# EFM8_Tag-Connect.net
KiCad netlist of a schematic drawn in EAGLE
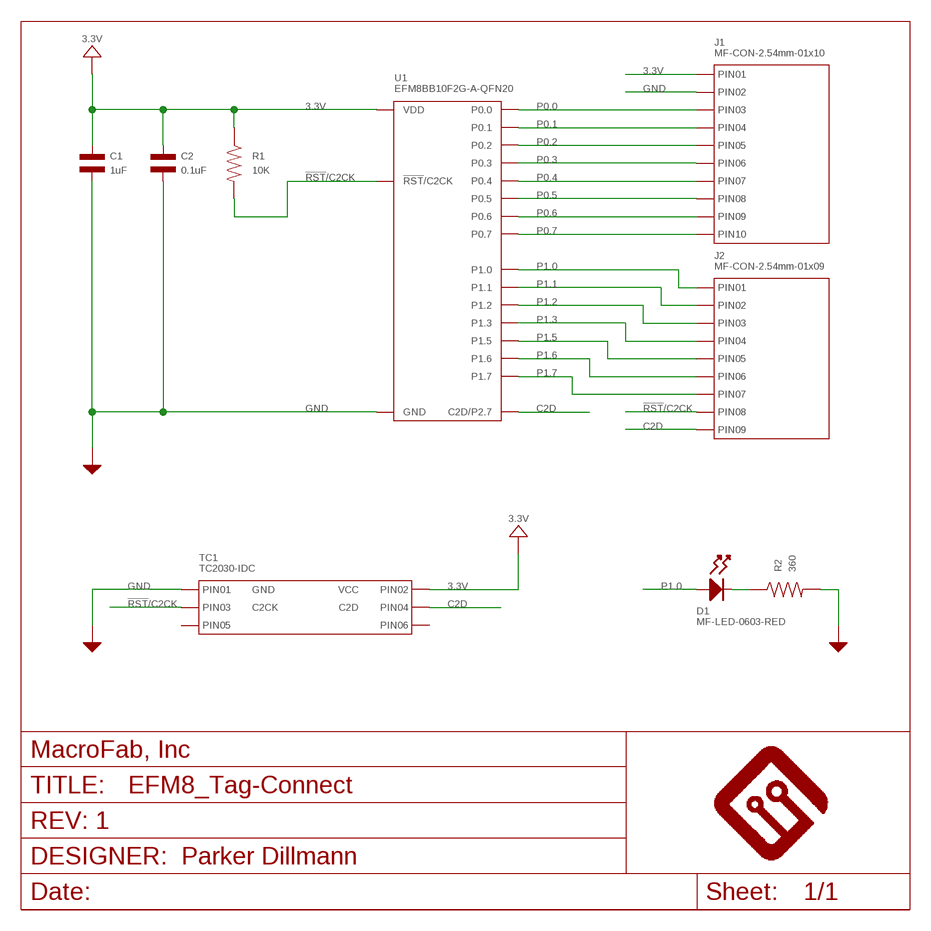
[diagram p0: schematic, sheet 1]

(export (version "E")
  (design (tool "Eeschema 10.0.6"))
  (components
    (comp (ref "C1")
      (value "1uF")
      (footprint "eagle-import:C0402")
      (fields (field (name "MPN") "MF-CAP-0402-1uF"))
      (libsource (lib "eagle-import") (part "CAPACITOR_NP_0402"))
    )
    (comp (ref "C2")
      (value "0.1uF")
      (footprint "eagle-import:C0402")
      (fields (field (name "MPN") "MF-CAP-0402-0.1uF"))
      (libsource (lib "eagle-import") (part "CAPACITOR_NP_0402"))
    )
    (comp (ref "D1")
      (value "MF-LED-0603-RED")
      (footprint "eagle-import:LED0603")
      (fields (field (name "HOUSEPART") "YES"))
      (libsource (lib "eagle-import") (part "LED_SINGLE-0603-RED"))
    )
    (comp (ref "FRAME1")
      (value "MF_FRAMEDEFAULT")
      (footprint "eagle-import:MF_FRAME_DEFAULT")
      (fields
        (field (name "HOUSEPART") "0")
        (field (name "DNAME") "Parker Dillmann")
        (field (name "REVNUM") "REV: 1")
      )
      (libsource (lib "eagle-import") (part "MF_FRAMEDEFAULT"))
    )
    (comp (ref "J1")
      (value "MF-CON-2.54mm-01x10")
      (footprint "eagle-import:PTH_2.54MM_01X10")
      (fields (field (name "HOUSEPART") "YES"))
      (libsource (lib "eagle-import") (part "CON_01X10_PTH_2.54MM"))
    )
    (comp (ref "J2")
      (value "MF-CON-2.54mm-01x09")
      (footprint "eagle-import:PTH_2.54MM_01X09")
      (fields (field (name "HOUSEPART") "YES"))
      (libsource (lib "eagle-import") (part "CON_01X09_PTH_2.54MM"))
    )
    (comp (ref "R1")
      (value "10K")
      (footprint "eagle-import:R0402")
      (fields (field (name "MPN") "MF-RES-0402-10K"))
      (libsource (lib "eagle-import") (part "RESISTOR_0402"))
    )
    (comp (ref "R2")
      (value "360")
      (footprint "eagle-import:R0402")
      (fields (field (name "MPN") "MF-RES-0402-360"))
      (libsource (lib "eagle-import") (part "RESISTOR_0402"))
    )
    (comp (ref "TC1")
      (value "TC2030-IDC")
      (footprint "eagle-import:TC2030-IDC-FP")
      (fields (field (name "HOUSEPART") "NO"))
      (libsource (lib "eagle-import") (part "CON_02X03_TC2030-IDC_SILABS2TC"))
    )
    (comp (ref "U1")
      (value "EFM8BB10F2G-A-QFN20")
      (footprint "eagle-import:EFM8BB10F(2_4_8)G-A-QFN20")
      (fields (field (name "HOUSEPART") "NO") (field (name "MPN") "EFM8BB10F2G-A-QFN20"))
      (libsource (lib "eagle-import") (part "EFM8BB10F(2/4/8)G-A-QFN20"))
    )
  )
  (nets
    (net (code "1") (name "/C2D") (class "Default")
      (node (ref "J2") (pin "P$9") (pinfunction "PIN9_P$9") (pintype "bidirectional"))
      (node (ref "TC1") (pin "P$4") (pinfunction "PIN4_P$4") (pintype "bidirectional"))
      (node (ref "U1") (pin "P$6") (pinfunction "C2D/P2.7_P$6") (pintype "bidirectional"))
    )
    (net (code "2") (name "/P0.0") (class "Default")
      (node (ref "J1") (pin "P$3") (pinfunction "PIN3_P$3") (pintype "bidirectional"))
      (node (ref "U1") (pin "P$2") (pinfunction "P0.0_P$2") (pintype "bidirectional"))
    )
    (net (code "3") (name "/P0.1") (class "Default")
      (node (ref "J1") (pin "P$4") (pinfunction "PIN4_P$4") (pintype "bidirectional"))
      (node (ref "U1") (pin "P$1") (pinfunction "P0.1_P$1") (pintype "bidirectional"))
    )
    (net (code "4") (name "/P0.2") (class "Default")
      (node (ref "J1") (pin "P$5") (pinfunction "PIN5_P$5") (pintype "bidirectional"))
      (node (ref "U1") (pin "P$20") (pinfunction "P0.2_P$20") (pintype "bidirectional"))
    )
    (net (code "5") (name "/P0.3") (class "Default")
      (node (ref "J1") (pin "P$6") (pinfunction "PIN6_P$6") (pintype "bidirectional"))
      (node (ref "U1") (pin "P$19") (pinfunction "P0.3_P$19") (pintype "bidirectional"))
    )
    (net (code "6") (name "/P0.4") (class "Default")
      (node (ref "J1") (pin "P$7") (pinfunction "PIN7_P$7") (pintype "bidirectional"))
      (node (ref "U1") (pin "P$18") (pinfunction "P0.4_P$18") (pintype "bidirectional"))
    )
    (net (code "7") (name "/P0.5") (class "Default")
      (node (ref "J1") (pin "P$8") (pinfunction "PIN8_P$8") (pintype "bidirectional"))
      (node (ref "U1") (pin "P$17") (pinfunction "P0.5_P$17") (pintype "bidirectional"))
    )
    (net (code "8") (name "/P0.6") (class "Default")
      (node (ref "J1") (pin "P$9") (pinfunction "PIN9_P$9") (pintype "bidirectional"))
      (node (ref "U1") (pin "P$16") (pinfunction "P0.6_P$16") (pintype "bidirectional"))
    )
    (net (code "9") (name "/P0.7") (class "Default")
      (node (ref "J1") (pin "P$10") (pinfunction "PIN10_P$10") (pintype "bidirectional"))
      (node (ref "U1") (pin "P$15") (pinfunction "P0.7_P$15") (pintype "bidirectional"))
    )
    (net (code "10") (name "/P1.0") (class "Default")
      (node (ref "D1") (pin "ANODE") (pinfunction "ANODE_ANODE") (pintype "power_in"))
      (node (ref "J2") (pin "P$1") (pinfunction "PIN1_P$1") (pintype "bidirectional"))
      (node (ref "U1") (pin "P$14") (pinfunction "P1.0_P$14") (pintype "bidirectional"))
    )
    (net (code "11") (name "/P1.1") (class "Default")
      (node (ref "J2") (pin "P$2") (pinfunction "PIN2_P$2") (pintype "bidirectional"))
      (node (ref "U1") (pin "P$13") (pinfunction "P1.1_P$13") (pintype "bidirectional"))
    )
    (net (code "12") (name "/P1.2") (class "Default")
      (node (ref "J2") (pin "P$3") (pinfunction "PIN3_P$3") (pintype "bidirectional"))
      (node (ref "U1") (pin "P$11") (pinfunction "P1.2_P$11") (pintype "bidirectional"))
    )
    (net (code "13") (name "/P1.3") (class "Default")
      (node (ref "J2") (pin "P$4") (pinfunction "PIN4_P$4") (pintype "bidirectional"))
      (node (ref "U1") (pin "P$10") (pinfunction "P1.3_P$10") (pintype "bidirectional"))
    )
    (net (code "14") (name "/P1.5") (class "Default")
      (node (ref "J2") (pin "P$5") (pinfunction "PIN5_P$5") (pintype "bidirectional"))
      (node (ref "U1") (pin "P$8") (pinfunction "P1.5_P$8") (pintype "bidirectional"))
    )
    (net (code "15") (name "/P1.6") (class "Default")
      (node (ref "J2") (pin "P$6") (pinfunction "PIN6_P$6") (pintype "bidirectional"))
      (node (ref "U1") (pin "P$7") (pinfunction "P1.6_P$7") (pintype "bidirectional"))
    )
    (net (code "16") (name "/P1.7") (class "Default")
      (node (ref "J2") (pin "P$7") (pinfunction "PIN7_P$7") (pintype "bidirectional"))
      (node (ref "U1") (pin "P$9") (pinfunction "P1.7_P$9") (pintype "bidirectional"))
    )
    (net (code "17") (name "/~{RST}{slash}C2CK") (class "Default")
      (node (ref "J2") (pin "P$8") (pinfunction "PIN8_P$8") (pintype "bidirectional"))
      (node (ref "R1") (pin "P$2") (pinfunction "P$2_P$2") (pintype "passive"))
      (node (ref "TC1") (pin "P$3") (pinfunction "PIN3_P$3") (pintype "bidirectional"))
      (node (ref "U1") (pin "P$5") (pinfunction "~{RST}/C2CK_P$5") (pintype "bidirectional"))
    )
    (net (code "18") (name "3.3V") (class "Default")
      (node (ref "C1") (pin "P$1") (pinfunction "P$1_P$1") (pintype "passive"))
      (node (ref "C2") (pin "P$1") (pinfunction "P$1_P$1") (pintype "passive"))
      (node (ref "J1") (pin "P$1") (pinfunction "PIN1_P$1") (pintype "bidirectional"))
      (node (ref "R1") (pin "P$1") (pinfunction "P$1_P$1") (pintype "passive"))
      (node (ref "TC1") (pin "P$2") (pinfunction "PIN2_P$2") (pintype "bidirectional"))
      (node (ref "U1") (pin "P$4") (pinfunction "VDD_P$4") (pintype "bidirectional"))
    )
    (net (code "19") (name "GND_RAIL") (class "Default")
      (node (ref "C1") (pin "P$2") (pinfunction "P$2_P$2") (pintype "passive"))
      (node (ref "C2") (pin "P$2") (pinfunction "P$2_P$2") (pintype "passive"))
      (node (ref "J1") (pin "P$2") (pinfunction "PIN2_P$2") (pintype "bidirectional"))
      (node (ref "R2") (pin "P$2") (pinfunction "P$2_P$2") (pintype "passive"))
      (node (ref "TC1") (pin "P$1") (pinfunction "PIN1_P$1") (pintype "bidirectional"))
      (node (ref "U1") (pin "P$12") (pinfunction "GND_P$12") (pintype "bidirectional"))
      (node (ref "U1") (pin "P$3") (pinfunction "GND_P$3") (pintype "bidirectional"))
      (node (ref "U1") (pin "PAD") (pinfunction "GND_PAD") (pintype "bidirectional"))
    )
    (net (code "20") (name "Net-(D1-PadCATHODE)") (class "Default")
      (node (ref "D1") (pin "CATHODE") (pinfunction "CATHODE_CATHODE") (pintype "power_in"))
      (node (ref "R2") (pin "P$1") (pinfunction "P$1_P$1") (pintype "passive"))
    )
    (net (code "21") (name "unconnected-(TC1-PIN5-PadP$5)") (class "Default")
      (node (ref "TC1") (pin "P$5") (pinfunction "PIN5_P$5") (pintype "bidirectional"))
    )
    (net (code "22") (name "unconnected-(TC1-PIN6-PadP$6)") (class "Default")
      (node (ref "TC1") (pin "P$6") (pinfunction "PIN6_P$6") (pintype "bidirectional"))
    )
  )
)
